# Teensy_Intan_Module_JE_20170512.net
KiCad netlist of a schematic drawn in EAGLE
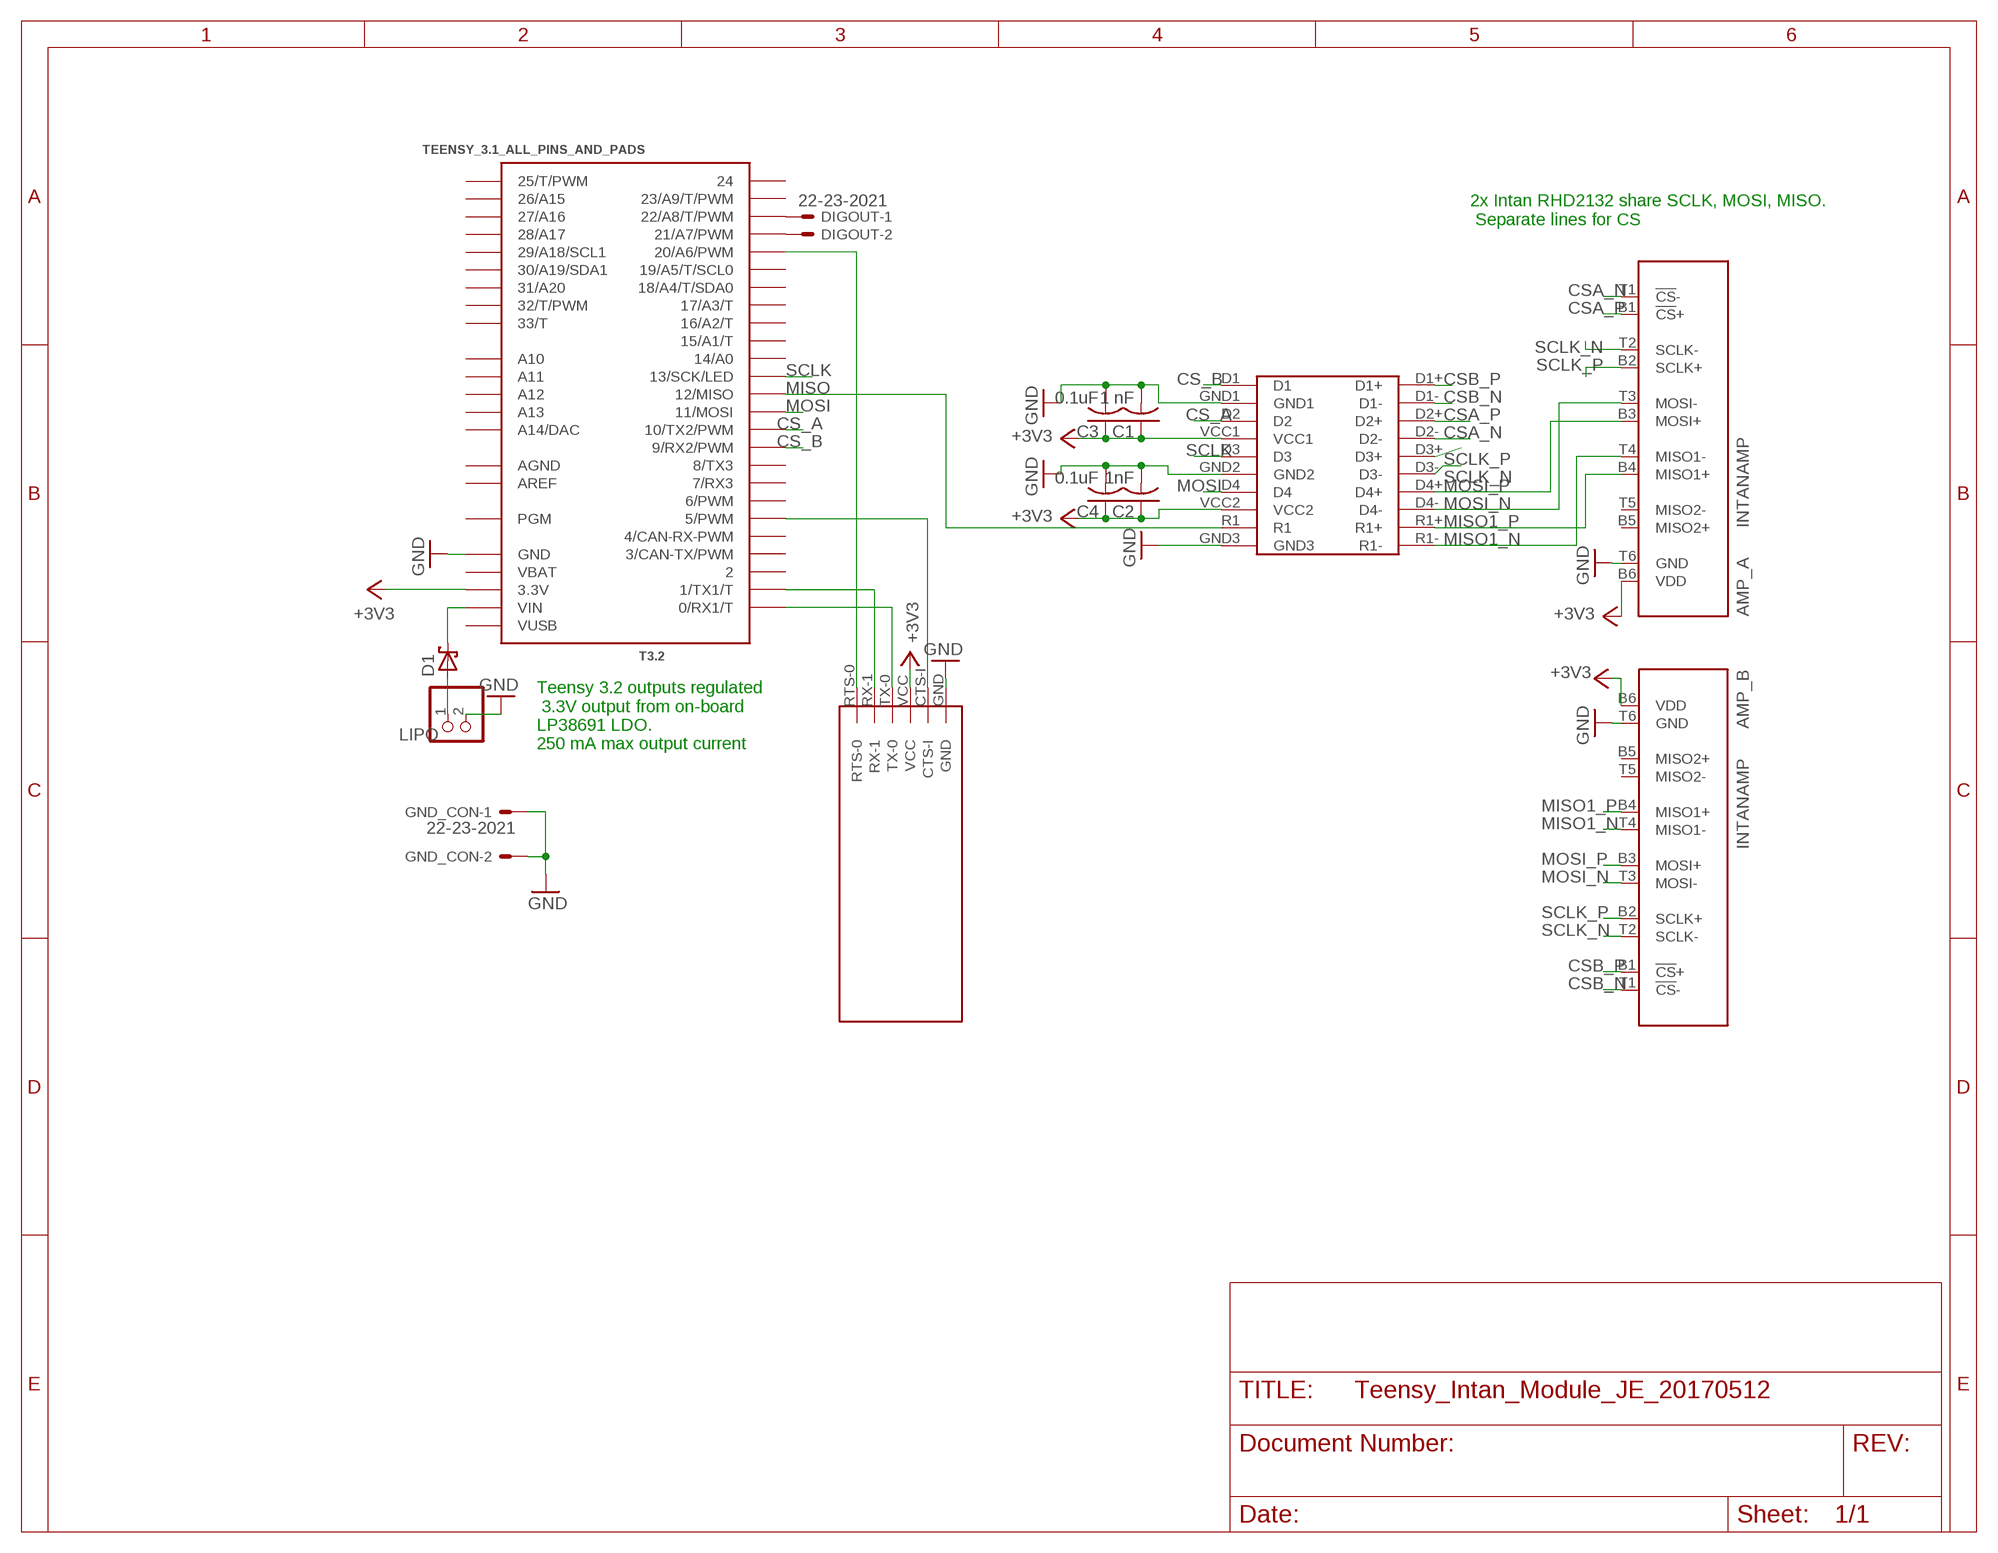
[diagram p0: schematic, sheet 1]

(export (version "E")
  (design (tool "Eeschema 10.0.6"))
  (components
    (comp (ref "AMP_A")
      (value "INTANAMP")
      (footprint "eagle-import:AMPBOARD")
      (libsource (lib "eagle-import") (part "INTANAMP"))
    )
    (comp (ref "AMP_B")
      (value "INTANAMP")
      (footprint "eagle-import:AMPBOARD")
      (libsource (lib "eagle-import") (part "INTANAMP"))
    )
    (comp (ref "C1")
      (value "1 nF")
      (footprint "eagle-import:C025-024X044")
      (libsource (lib "eagle-import") (part "C-US025-024X044"))
    )
    (comp (ref "C2")
      (value "1nF")
      (footprint "eagle-import:C025-024X044")
      (libsource (lib "eagle-import") (part "C-US025-024X044"))
    )
    (comp (ref "C3")
      (value "0.1uF")
      (footprint "eagle-import:C025-024X044")
      (libsource (lib "eagle-import") (part "C-US025-024X044"))
    )
    (comp (ref "C4")
      (value "0.1uF")
      (footprint "eagle-import:C025-024X044")
      (libsource (lib "eagle-import") (part "C-US025-024X044"))
    )
    (comp (ref "D1")
      (value "SCHOTTKY-DIODEDO41-7")
      (footprint "eagle-import:DO41-7")
      (libsource (lib "eagle-import") (part "SCHOTTKY-DIODEDO41-7"))
    )
    (comp (ref "DIGOUT")
      (value "22-23-2021")
      (footprint "eagle-import:22-23-2021")
      (fields (field (name "MF") "MOLEX"))
      (libsource (lib "eagle-import") (part "22-23-2021"))
    )
    (comp (ref "GND_CON")
      (value "22-23-2021")
      (footprint "eagle-import:22-23-2021")
      (fields (field (name "MF") "MOLEX"))
      (libsource (lib "eagle-import") (part "22-23-2021"))
    )
    (comp (ref "LIPO")
      (value "LIPO_BAT")
      (footprint "eagle-import:JST-PH-2-THM")
      (libsource (lib "eagle-import") (part "JST_2PIN-THM"))
    )
    (comp (ref "RN42")
      (value "RN42")
      (footprint "eagle-import:RN42")
      (libsource (lib "eagle-import") (part "RN42"))
    )
    (comp (ref "T3.2")
      (value "TEENSY_3.1_ALL_PINS_AND_PADS")
      (footprint "eagle-import:TEENSY_3.1_ALLPINS")
      (libsource (lib "eagle-import") (part "TEENSY_3.1_ALL_PINS_AND_PADS"))
    )
    (comp (ref "U$1")
      (value "SCHMARTBOARD20PIN")
      (footprint "eagle-import:SCHMARTBOARD20PIN")
      (libsource (lib "eagle-import") (part "SCHMARTBOARD20PIN"))
    )
  )
  (nets
    (net (code "1") (name "+3V3") (class "Default")
      (node (ref "AMP_A") (pin "B6") (pinfunction "VDD_B6") (pintype "bidirectional"))
      (node (ref "AMP_B") (pin "B6") (pinfunction "VDD_B6") (pintype "bidirectional"))
      (node (ref "C1") (pin "1") (pinfunction "1_1") (pintype "passive"))
      (node (ref "C2") (pin "1") (pinfunction "1_1") (pintype "passive"))
      (node (ref "C3") (pin "1") (pinfunction "1_1") (pintype "passive"))
      (node (ref "C4") (pin "1") (pinfunction "1_1") (pintype "passive"))
      (node (ref "RN42") (pin "VCC") (pinfunction "VCC_VCC") (pintype "bidirectional"))
      (node (ref "T3.2") (pin "3.3V") (pinfunction "3.3V_3.3V") (pintype "power_in"))
      (node (ref "T3.2") (pin "3.3V1") (pinfunction "3.3V_3.3V1") (pintype "power_in"))
      (node (ref "T3.2") (pin "3.3V2") (pinfunction "3.3V_3.3V2") (pintype "power_in"))
      (node (ref "U$1") (pin "VCC1") (pinfunction "VCC1_VCC1") (pintype "bidirectional"))
      (node (ref "U$1") (pin "VCC2") (pinfunction "VCC2_VCC2") (pintype "bidirectional"))
    )
    (net (code "2") (name "/AGND") (class "Default")
      (node (ref "T3.2") (pin "AGND") (pinfunction "AGND_AGND") (pintype "power_in"))
    )
    (net (code "3") (name "/AREF") (class "Default")
      (node (ref "T3.2") (pin "AREF") (pinfunction "AREF_AREF") (pintype "power_in"))
    )
    (net (code "4") (name "/CSA_N") (class "Default")
      (node (ref "AMP_A") (pin "T1") (pinfunction "~{CS}-_T1") (pintype "bidirectional"))
      (node (ref "U$1") (pin "D2-") (pinfunction "D2-_D2-") (pintype "bidirectional"))
    )
    (net (code "5") (name "/CSA_P") (class "Default")
      (node (ref "AMP_A") (pin "B1") (pinfunction "~{CS}+_B1") (pintype "bidirectional"))
      (node (ref "U$1") (pin "D2+") (pinfunction "D2+_D2+") (pintype "bidirectional"))
    )
    (net (code "6") (name "/CSB_N") (class "Default")
      (node (ref "AMP_B") (pin "T1") (pinfunction "~{CS}-_T1") (pintype "bidirectional"))
      (node (ref "U$1") (pin "D1-") (pinfunction "D1-_D1-") (pintype "bidirectional"))
    )
    (net (code "7") (name "/CSB_P") (class "Default")
      (node (ref "AMP_B") (pin "B1") (pinfunction "~{CS}+_B1") (pintype "bidirectional"))
      (node (ref "U$1") (pin "D1+") (pinfunction "D1+_D1+") (pintype "bidirectional"))
    )
    (net (code "8") (name "/CS_A") (class "Default")
      (node (ref "T3.2") (pin "10") (pinfunction "10/TX2/PWM_10") (pintype "bidirectional"))
      (node (ref "U$1") (pin "D2") (pinfunction "D2_D2") (pintype "bidirectional"))
    )
    (net (code "9") (name "/CS_B") (class "Default")
      (node (ref "T3.2") (pin "9") (pinfunction "9/RX2/PWM_9") (pintype "bidirectional"))
      (node (ref "U$1") (pin "D1") (pinfunction "D1_D1") (pintype "bidirectional"))
    )
    (net (code "10") (name "/MISO") (class "Default")
      (node (ref "T3.2") (pin "12") (pinfunction "12/MISO_12") (pintype "bidirectional"))
      (node (ref "U$1") (pin "R1") (pinfunction "R1_R1") (pintype "bidirectional"))
    )
    (net (code "11") (name "/MISO1_N") (class "Default")
      (node (ref "AMP_A") (pin "T4") (pinfunction "MISO1-_T4") (pintype "bidirectional"))
      (node (ref "AMP_B") (pin "T4") (pinfunction "MISO1-_T4") (pintype "bidirectional"))
      (node (ref "U$1") (pin "R1-") (pinfunction "R1-_R1-") (pintype "bidirectional"))
    )
    (net (code "12") (name "/MISO1_P") (class "Default")
      (node (ref "AMP_A") (pin "B4") (pinfunction "MISO1+_B4") (pintype "bidirectional"))
      (node (ref "AMP_B") (pin "B4") (pinfunction "MISO1+_B4") (pintype "bidirectional"))
      (node (ref "U$1") (pin "R1+") (pinfunction "R1+_R1+") (pintype "bidirectional"))
    )
    (net (code "13") (name "/MOSI") (class "Default")
      (node (ref "T3.2") (pin "11") (pinfunction "11/MOSI_11") (pintype "bidirectional"))
      (node (ref "U$1") (pin "D4") (pinfunction "D4_D4") (pintype "bidirectional"))
    )
    (net (code "14") (name "/MOSI_N") (class "Default")
      (node (ref "AMP_A") (pin "T3") (pinfunction "MOSI-_T3") (pintype "bidirectional"))
      (node (ref "AMP_B") (pin "T3") (pinfunction "MOSI-_T3") (pintype "bidirectional"))
      (node (ref "U$1") (pin "D4-") (pinfunction "D4-_D4-") (pintype "bidirectional"))
    )
    (net (code "15") (name "/MOSI_P") (class "Default")
      (node (ref "AMP_A") (pin "B3") (pinfunction "MOSI+_B3") (pintype "bidirectional"))
      (node (ref "AMP_B") (pin "B3") (pinfunction "MOSI+_B3") (pintype "bidirectional"))
      (node (ref "U$1") (pin "D4+") (pinfunction "D4+_D4+") (pintype "bidirectional"))
    )
    (net (code "16") (name "/SCLK") (class "Default")
      (node (ref "T3.2") (pin "13") (pinfunction "13/SCK/LED_13") (pintype "bidirectional"))
      (node (ref "U$1") (pin "D3") (pinfunction "D3_D3") (pintype "bidirectional"))
    )
    (net (code "17") (name "/SCLK_N") (class "Default")
      (node (ref "AMP_A") (pin "T2") (pinfunction "SCLK-_T2") (pintype "bidirectional"))
      (node (ref "AMP_B") (pin "T2") (pinfunction "SCLK-_T2") (pintype "bidirectional"))
      (node (ref "U$1") (pin "D3-") (pinfunction "D3-_D3-") (pintype "bidirectional"))
    )
    (net (code "18") (name "/SCLK_P") (class "Default")
      (node (ref "AMP_A") (pin "B2") (pinfunction "SCLK+_B2") (pintype "bidirectional"))
      (node (ref "AMP_B") (pin "B2") (pinfunction "SCLK+_B2") (pintype "bidirectional"))
      (node (ref "U$1") (pin "D3+") (pinfunction "D3+_D3+") (pintype "bidirectional"))
    )
    (net (code "19") (name "/VBAT") (class "Default")
      (node (ref "T3.2") (pin "VBAT") (pinfunction "VBAT_VBAT") (pintype "power_in"))
    )
    (net (code "20") (name "/VUSB") (class "Default")
      (node (ref "T3.2") (pin "VUSB") (pinfunction "VUSB_VUSB") (pintype "power_in"))
    )
    (net (code "21") (name "GND") (class "Default")
      (node (ref "AMP_A") (pin "T6") (pinfunction "GND_T6") (pintype "power_in"))
      (node (ref "AMP_B") (pin "T6") (pinfunction "GND_T6") (pintype "power_in"))
      (node (ref "C1") (pin "2") (pinfunction "2_2") (pintype "passive"))
      (node (ref "C2") (pin "2") (pinfunction "2_2") (pintype "passive"))
      (node (ref "C3") (pin "2") (pinfunction "2_2") (pintype "passive"))
      (node (ref "C4") (pin "2") (pinfunction "2_2") (pintype "passive"))
      (node (ref "GND_CON") (pin "1") (pinfunction "S_1") (pintype "passive"))
      (node (ref "GND_CON") (pin "2") (pinfunction "S_2") (pintype "passive"))
      (node (ref "LIPO") (pin "2") (pinfunction "1_2") (pintype "passive"))
      (node (ref "RN42") (pin "GND") (pinfunction "GND_GND") (pintype "bidirectional"))
      (node (ref "T3.2") (pin "GND") (pinfunction "GND_GND") (pintype "power_in"))
      (node (ref "T3.2") (pin "GND1") (pinfunction "GND_GND1") (pintype "power_in"))
      (node (ref "T3.2") (pin "GND2") (pinfunction "GND_GND2") (pintype "power_in"))
      (node (ref "U$1") (pin "GND1") (pinfunction "GND1_GND1") (pintype "bidirectional"))
      (node (ref "U$1") (pin "GND2") (pinfunction "GND2_GND2") (pintype "bidirectional"))
      (node (ref "U$1") (pin "GND3") (pinfunction "GND3_GND3") (pintype "bidirectional"))
    )
    (net (code "22") (name "Net-(D1-PadC)") (class "Default")
      (node (ref "D1") (pin "C") (pinfunction "C_C") (pintype "passive"))
      (node (ref "T3.2") (pin "VIN") (pinfunction "VIN_VIN") (pintype "power_in"))
    )
    (net (code "23") (name "Net-(DIGOUTA-S)") (class "Default")
      (node (ref "DIGOUT") (pin "1") (pinfunction "S_1") (pintype "passive"))
      (node (ref "T3.2") (pin "22/A8") (pinfunction "22/A8/T/PWM_22/A8") (pintype "bidirectional"))
    )
    (net (code "24") (name "Net-(DIGOUTB-S)") (class "Default")
      (node (ref "DIGOUT") (pin "2") (pinfunction "S_2") (pintype "passive"))
      (node (ref "T3.2") (pin "21/A7") (pinfunction "21/A7/PWM_21/A7") (pintype "bidirectional"))
    )
    (net (code "25") (name "Net-(LIPO-2)") (class "Default")
      (node (ref "D1") (pin "A") (pinfunction "A_A") (pintype "passive"))
      (node (ref "LIPO") (pin "1") (pinfunction "2_1") (pintype "passive"))
    )
    (net (code "26") (name "Net-(T3.2-0{slash}RX1{slash}T)") (class "Default")
      (node (ref "RN42") (pin "TX-0") (pinfunction "TX-0_TX-0") (pintype "bidirectional"))
      (node (ref "T3.2") (pin "0") (pinfunction "0/RX1/T_0") (pintype "bidirectional"))
    )
    (net (code "27") (name "Net-(T3.2-1{slash}TX1{slash}T)") (class "Default")
      (node (ref "RN42") (pin "RX-1") (pinfunction "RX-1_RX-1") (pintype "bidirectional"))
      (node (ref "T3.2") (pin "1") (pinfunction "1/TX1/T_1") (pintype "bidirectional"))
    )
    (net (code "28") (name "Net-(T3.2-5{slash}PWM)") (class "Default")
      (node (ref "RN42") (pin "CTS-I") (pinfunction "CTS-I_CTS-I") (pintype "bidirectional"))
      (node (ref "T3.2") (pin "5") (pinfunction "5/PWM_5") (pintype "bidirectional"))
    )
    (net (code "29") (name "Net-(T3.2-20{slash}A6{slash}PWM)") (class "Default")
      (node (ref "RN42") (pin "RTS-0") (pinfunction "RTS-0_RTS-0") (pintype "bidirectional"))
      (node (ref "T3.2") (pin "20/A6") (pinfunction "20/A6/PWM_20/A6") (pintype "bidirectional"))
    )
    (net (code "30") (name "unconnected-(AMP_A-MISO2+-PadB5)") (class "Default")
      (node (ref "AMP_A") (pin "B5") (pinfunction "MISO2+_B5") (pintype "bidirectional"))
    )
    (net (code "31") (name "unconnected-(AMP_A-MISO2--PadT5)") (class "Default")
      (node (ref "AMP_A") (pin "T5") (pinfunction "MISO2-_T5") (pintype "bidirectional"))
    )
    (net (code "32") (name "unconnected-(AMP_B-MISO2+-PadB5)") (class "Default")
      (node (ref "AMP_B") (pin "B5") (pinfunction "MISO2+_B5") (pintype "bidirectional"))
    )
    (net (code "33") (name "unconnected-(AMP_B-MISO2--PadT5)") (class "Default")
      (node (ref "AMP_B") (pin "T5") (pinfunction "MISO2-_T5") (pintype "bidirectional"))
    )
    (net (code "34") (name "unconnected-(T3.2-3{slash}CAN-TX{slash}PWM-Pad3)") (class "Default")
      (node (ref "T3.2") (pin "3") (pinfunction "3/CAN-TX/PWM_3") (pintype "bidirectional"))
    )
    (net (code "35") (name "unconnected-(T3.2-4{slash}CAN-RX-PWM-Pad4)") (class "Default")
      (node (ref "T3.2") (pin "4") (pinfunction "4/CAN-RX-PWM_4") (pintype "bidirectional"))
    )
    (net (code "36") (name "unconnected-(T3.2-6{slash}PWM-Pad6)") (class "Default")
      (node (ref "T3.2") (pin "6") (pinfunction "6/PWM_6") (pintype "bidirectional"))
    )
    (net (code "37") (name "unconnected-(T3.2-7{slash}RX3-Pad7)") (class "Default")
      (node (ref "T3.2") (pin "7") (pinfunction "7/RX3_7") (pintype "bidirectional"))
    )
    (net (code "38") (name "unconnected-(T3.2-8{slash}TX3-Pad8)") (class "Default")
      (node (ref "T3.2") (pin "8") (pinfunction "8/TX3_8") (pintype "bidirectional"))
    )
    (net (code "39") (name "unconnected-(T3.2-15{slash}A1{slash}T-Pad15{slash}A1)") (class "Default")
      (node (ref "T3.2") (pin "15/A1") (pinfunction "15/A1/T_15/A1") (pintype "bidirectional"))
    )
    (net (code "40") (name "unconnected-(T3.2-16{slash}A2{slash}T-Pad16{slash}A2)") (class "Default")
      (node (ref "T3.2") (pin "16/A2") (pinfunction "16/A2/T_16/A2") (pintype "bidirectional"))
    )
    (net (code "41") (name "unconnected-(T3.2-17{slash}A3{slash}T-Pad17{slash}A3)") (class "Default")
      (node (ref "T3.2") (pin "17/A3") (pinfunction "17/A3/T_17/A3") (pintype "bidirectional"))
    )
    (net (code "42") (name "unconnected-(T3.2-18{slash}A4{slash}T{slash}SDA0-Pad18{slash}A4)") (class "Default")
      (node (ref "T3.2") (pin "18/A4") (pinfunction "18/A4/T/SDA0_18/A4") (pintype "bidirectional"))
    )
    (net (code "43") (name "unconnected-(T3.2-19{slash}A5{slash}T{slash}SCL0-Pad19{slash}A5)") (class "Default")
      (node (ref "T3.2") (pin "19/A5") (pinfunction "19/A5/T/SCL0_19/A5") (pintype "bidirectional"))
    )
    (net (code "44") (name "unconnected-(T3.2-23{slash}A9{slash}T{slash}PWM-Pad23{slash}A9)") (class "Default")
      (node (ref "T3.2") (pin "23/A9") (pinfunction "23/A9/T/PWM_23/A9") (pintype "bidirectional"))
    )
    (net (code "45") (name "unconnected-(T3.2-25{slash}T{slash}PWM-Pad25)") (class "Default")
      (node (ref "T3.2") (pin "25") (pinfunction "25/T/PWM_25") (pintype "bidirectional"))
    )
    (net (code "46") (name "unconnected-(T3.2-26{slash}A15-Pad26)") (class "Default")
      (node (ref "T3.2") (pin "26") (pinfunction "26/A15_26") (pintype "bidirectional"))
    )
    (net (code "47") (name "unconnected-(T3.2-27{slash}A16-Pad27)") (class "Default")
      (node (ref "T3.2") (pin "27") (pinfunction "27/A16_27") (pintype "bidirectional"))
    )
    (net (code "48") (name "unconnected-(T3.2-28{slash}A17-Pad28)") (class "Default")
      (node (ref "T3.2") (pin "28") (pinfunction "28/A17_28") (pintype "bidirectional"))
    )
    (net (code "49") (name "unconnected-(T3.2-29{slash}A18{slash}SCL1-Pad29)") (class "Default")
      (node (ref "T3.2") (pin "29") (pinfunction "29/A18/SCL1_29") (pintype "bidirectional"))
    )
    (net (code "50") (name "unconnected-(T3.2-30{slash}A19{slash}SDA1-Pad30)") (class "Default")
      (node (ref "T3.2") (pin "30") (pinfunction "30/A19/SDA1_30") (pintype "bidirectional"))
    )
    (net (code "51") (name "unconnected-(T3.2-31{slash}A20-Pad31)") (class "Default")
      (node (ref "T3.2") (pin "31") (pinfunction "31/A20_31") (pintype "bidirectional"))
    )
    (net (code "52") (name "unconnected-(T3.2-32{slash}T{slash}PWM-Pad32)") (class "Default")
      (node (ref "T3.2") (pin "32") (pinfunction "32/T/PWM_32") (pintype "bidirectional"))
    )
    (net (code "53") (name "unconnected-(T3.2-33{slash}T-Pad33)") (class "Default")
      (node (ref "T3.2") (pin "33") (pinfunction "33/T_33") (pintype "bidirectional"))
    )
    (net (code "54") (name "unconnected-(T3.2-A14{slash}DAC-PadA14)") (class "Default")
      (node (ref "T3.2") (pin "A14") (pinfunction "A14/DAC_A14") (pintype "bidirectional"))
    )
    (net (code "55") (name "unconnected-(T3.2-Pad2)") (class "Default")
      (node (ref "T3.2") (pin "2") (pinfunction "2_2") (pintype "bidirectional"))
    )
    (net (code "56") (name "unconnected-(T3.2-Pad14{slash}A0)") (class "Default")
      (node (ref "T3.2") (pin "14/A0") (pinfunction "14/A0_14/A0") (pintype "bidirectional"))
    )
    (net (code "57") (name "unconnected-(T3.2-Pad24)") (class "Default")
      (node (ref "T3.2") (pin "24") (pinfunction "24_24") (pintype "bidirectional"))
    )
    (net (code "58") (name "unconnected-(T3.2-PadA10)") (class "Default")
      (node (ref "T3.2") (pin "A10") (pinfunction "A10_A10") (pintype "bidirectional"))
    )
    (net (code "59") (name "unconnected-(T3.2-PadA11)") (class "Default")
      (node (ref "T3.2") (pin "A11") (pinfunction "A11_A11") (pintype "bidirectional"))
    )
    (net (code "60") (name "unconnected-(T3.2-PadA12)") (class "Default")
      (node (ref "T3.2") (pin "A12") (pinfunction "A12_A12") (pintype "bidirectional"))
    )
    (net (code "61") (name "unconnected-(T3.2-PadA13)") (class "Default")
      (node (ref "T3.2") (pin "A13") (pinfunction "A13_A13") (pintype "bidirectional"))
    )
    (net (code "62") (name "unconnected-(T3.2-PadPGM)") (class "Default")
      (node (ref "T3.2") (pin "PGM") (pinfunction "PGM_PGM") (pintype "bidirectional"))
    )
  )
)
